# arduino_uno_with_rs232.net
KiCad netlist of a schematic drawn in EAGLE
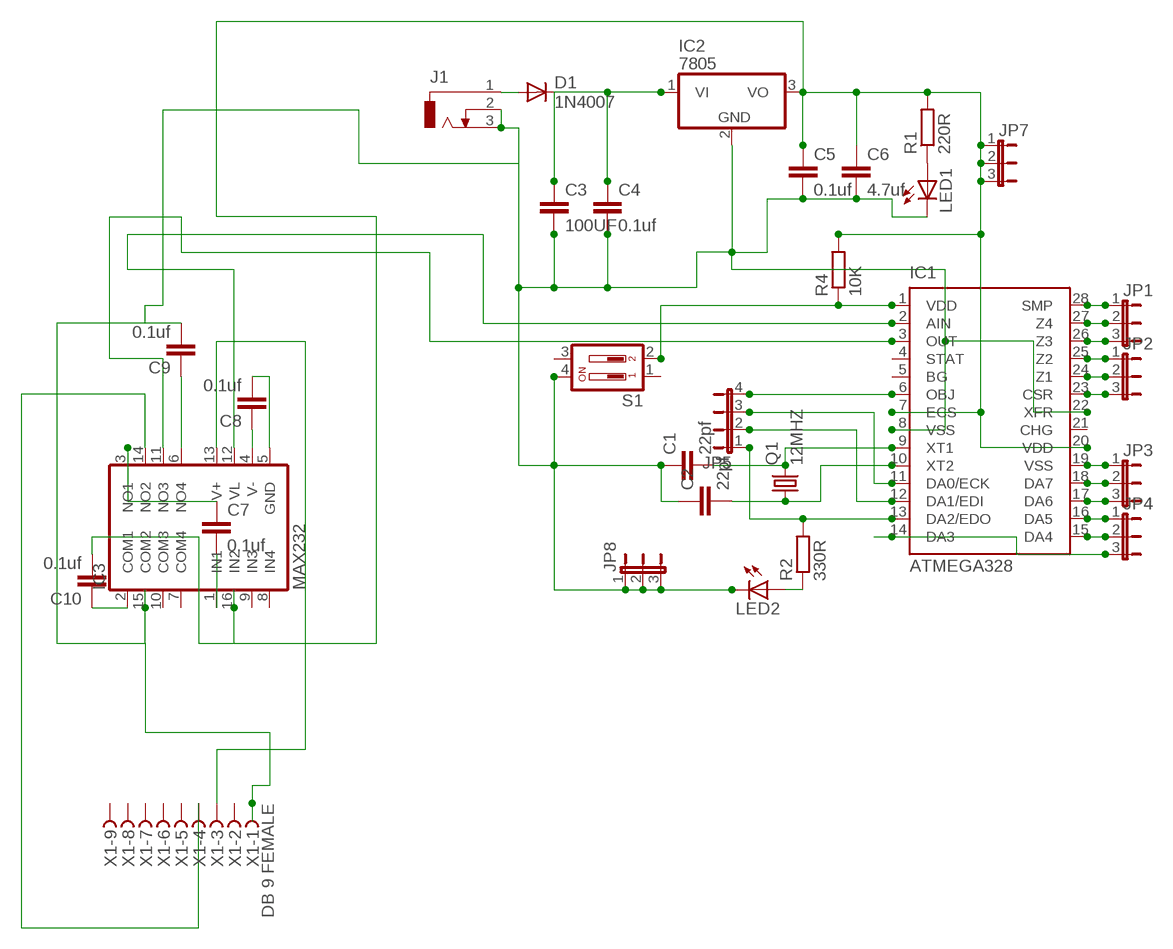
[diagram p0: schematic, sheet 1]

(export (version "E")
  (design (tool "Eeschema 10.0.6"))
  (components
    (comp (ref "C1")
      (value "22pf")
      (footprint "eagle-import:C2.5-2")
      (libsource (lib "eagle-import") (part "C2.5/2"))
    )
    (comp (ref "C2")
      (value "22pf")
      (footprint "eagle-import:C2.5-2")
      (libsource (lib "eagle-import") (part "C2.5/2"))
    )
    (comp (ref "C3")
      (value "100UF")
      (footprint "eagle-import:C2.5-2")
      (libsource (lib "eagle-import") (part "C2.5/2"))
    )
    (comp (ref "C4")
      (value "0.1uf")
      (footprint "eagle-import:C2.5-2")
      (libsource (lib "eagle-import") (part "C2.5/2"))
    )
    (comp (ref "C5")
      (value "0.1uf")
      (footprint "eagle-import:C2.5-2")
      (libsource (lib "eagle-import") (part "C2.5/2"))
    )
    (comp (ref "C6")
      (value "4.7uf")
      (footprint "eagle-import:C2.5-2")
      (libsource (lib "eagle-import") (part "C2.5/2"))
    )
    (comp (ref "C7")
      (value "0.1uf")
      (footprint "eagle-import:C2.5-3")
      (libsource (lib "eagle-import") (part "C2,5-3"))
    )
    (comp (ref "C8")
      (value "0.1uf")
      (footprint "eagle-import:C2.5-3")
      (libsource (lib "eagle-import") (part "C2,5-3"))
    )
    (comp (ref "C9")
      (value "0.1uf")
      (footprint "eagle-import:C2.5-3")
      (libsource (lib "eagle-import") (part "C2,5-3"))
    )
    (comp (ref "C10")
      (value "0.1uf")
      (footprint "eagle-import:C2.5-3")
      (libsource (lib "eagle-import") (part "C2,5-3"))
    )
    (comp (ref "D1")
      (value "1N4007")
      (footprint "eagle-import:DO41-10")
      (libsource (lib "eagle-import") (part "1N4004"))
    )
    (comp (ref "IC1")
      (value "ATMEGA328")
      (footprint "eagle-import:DIL28-3")
      (libsource (lib "eagle-import") (part "QT9701BD"))
    )
    (comp (ref "IC2")
      (value "7805")
      (footprint "eagle-import:TO220V")
      (libsource (lib "eagle-import") (part "78TV6"))
    )
    (comp (ref "IC3")
      (value "MAX232")
      (footprint "eagle-import:DIL16")
      (fields (field (name "MPN") "MAX313EPE+"))
      (libsource (lib "eagle-import") (part "MAX313PEE"))
    )
    (comp (ref "J1")
      (value "DCJ0303")
      (footprint "eagle-import:DCJ0303")
      (libsource (lib "eagle-import") (part "DCJ0303"))
    )
    (comp (ref "JP1")
      (value "JP2E")
      (footprint "eagle-import:JP2")
      (libsource (lib "eagle-import") (part "JP2E"))
    )
    (comp (ref "JP2")
      (value "JP2E")
      (footprint "eagle-import:JP2")
      (libsource (lib "eagle-import") (part "JP2E"))
    )
    (comp (ref "JP3")
      (value "JP2E")
      (footprint "eagle-import:JP2")
      (libsource (lib "eagle-import") (part "JP2E"))
    )
    (comp (ref "JP4")
      (value "JP2E")
      (footprint "eagle-import:JP2")
      (libsource (lib "eagle-import") (part "JP2E"))
    )
    (comp (ref "JP5")
      (value "JP4E")
      (footprint "eagle-import:JP4")
      (libsource (lib "eagle-import") (part "JP4E"))
    )
    (comp (ref "JP7")
      (value "JP2E")
      (footprint "eagle-import:JP2")
      (libsource (lib "eagle-import") (part "JP2E"))
    )
    (comp (ref "JP8")
      (value "JP2E")
      (footprint "eagle-import:JP2")
      (libsource (lib "eagle-import") (part "JP2E"))
    )
    (comp (ref "LED1")
      (value "LED3MM")
      (footprint "eagle-import:LED3MM")
      (libsource (lib "eagle-import") (part "LED3MM"))
    )
    (comp (ref "LED2")
      (value "LED3MM")
      (footprint "eagle-import:LED3MM")
      (libsource (lib "eagle-import") (part "LED3MM"))
    )
    (comp (ref "Q1")
      (value "12MHZ")
      (footprint "eagle-import:HC49_S")
      (libsource (lib "eagle-import") (part "CRYSTALHC49S"))
    )
    (comp (ref "R1")
      (value "220R")
      (footprint "eagle-import:0207_10")
      (libsource (lib "eagle-import") (part "R-EU_0207/10"))
    )
    (comp (ref "R2")
      (value "330R")
      (footprint "eagle-import:0207_10")
      (libsource (lib "eagle-import") (part "R-EU_0207/10"))
    )
    (comp (ref "R4")
      (value "10K")
      (footprint "eagle-import:0207_10")
      (libsource (lib "eagle-import") (part "R-EU_0207/10"))
    )
    (comp (ref "S1")
      (value "DP02")
      (footprint "eagle-import:DP-02")
      (fields (field (name "MPN") "MCDP02"))
      (libsource (lib "eagle-import") (part "DP02"))
    )
    (comp (ref "X1")
      (value "DB 9 FEMALE")
      (footprint "eagle-import:H2M09ST")
      (libsource (lib "eagle-import") (part "D-SUB9-H2M09ST"))
    )
  )
  (nets
    (net (code "1") (name "Net-(D1-PadA)") (class "Default")
      (node (ref "D1") (pin "A") (pinfunction "A_A") (pintype "passive"))
      (node (ref "J1") (pin "1") (pinfunction "1_1") (pintype "passive"))
    )
    (net (code "2") (name "Net-(IC1-AIN)") (class "Default")
      (node (ref "IC1") (pin "2") (pinfunction "AIN_2") (pintype "input"))
      (node (ref "IC3") (pin "12") (pinfunction "VL_12") (pintype "power_in"))
    )
    (net (code "3") (name "Net-(IC1-CSR)") (class "Default")
      (node (ref "IC1") (pin "23") (pinfunction "CSR_23") (pintype "output"))
      (node (ref "JP2") (pin "3") (pinfunction "3_3") (pintype "passive"))
    )
    (net (code "4") (name "Net-(IC1-DA0{slash}ECK)") (class "Default")
      (node (ref "IC1") (pin "11") (pinfunction "DA0/ECK_11") (pintype "output"))
      (node (ref "JP5") (pin "3") (pinfunction "3_3") (pintype "passive"))
    )
    (net (code "5") (name "Net-(IC1-DA1{slash}EDI)") (class "Default")
      (node (ref "IC1") (pin "12") (pinfunction "DA1/EDI_12") (pintype "output"))
      (node (ref "JP5") (pin "2") (pinfunction "2_2") (pintype "passive"))
    )
    (net (code "6") (name "Net-(IC1-DA2{slash}EDO)") (class "Default")
      (node (ref "IC1") (pin "13") (pinfunction "DA2/EDO_13") (pintype "output"))
      (node (ref "JP5") (pin "1") (pinfunction "1_1") (pintype "passive"))
      (node (ref "R2") (pin "2") (pinfunction "2_2") (pintype "passive"))
    )
    (net (code "7") (name "Net-(IC1-DA3)") (class "Default")
      (node (ref "IC1") (pin "14") (pinfunction "DA3_14") (pintype "output"))
      (node (ref "JP4") (pin "3") (pinfunction "3_3") (pintype "passive"))
    )
    (net (code "8") (name "Net-(IC1-DA4)") (class "Default")
      (node (ref "IC1") (pin "15") (pinfunction "DA4_15") (pintype "output"))
      (node (ref "JP4") (pin "2") (pinfunction "2_2") (pintype "passive"))
    )
    (net (code "9") (name "Net-(IC1-DA5)") (class "Default")
      (node (ref "IC1") (pin "16") (pinfunction "DA5_16") (pintype "output"))
      (node (ref "JP4") (pin "1") (pinfunction "1_1") (pintype "passive"))
    )
    (net (code "10") (name "Net-(IC1-DA6)") (class "Default")
      (node (ref "IC1") (pin "17") (pinfunction "DA6_17") (pintype "output"))
      (node (ref "JP3") (pin "3") (pinfunction "3_3") (pintype "passive"))
    )
    (net (code "11") (name "Net-(IC1-DA7)") (class "Default")
      (node (ref "IC1") (pin "18") (pinfunction "DA7_18") (pintype "output"))
      (node (ref "JP3") (pin "2") (pinfunction "2_2") (pintype "passive"))
    )
    (net (code "12") (name "Net-(IC1-ECS)") (class "Default")
      (node (ref "C10") (pin "2") (pinfunction "2_2") (pintype "passive"))
      (node (ref "C5") (pin "1") (pinfunction "1_1") (pintype "passive"))
      (node (ref "C6") (pin "1") (pinfunction "1_1") (pintype "passive"))
      (node (ref "IC1") (pin "20") (pinfunction "VDD_20") (pintype "input"))
      (node (ref "IC1") (pin "7") (pinfunction "ECS_7") (pintype "output"))
      (node (ref "IC2") (pin "3") (pinfunction "VO_3") (pintype "passive"))
      (node (ref "IC3") (pin "16") (pinfunction "IN2_16") (pintype "input"))
      (node (ref "JP7") (pin "1") (pinfunction "1_1") (pintype "passive"))
      (node (ref "JP7") (pin "2") (pinfunction "2_2") (pintype "passive"))
      (node (ref "JP7") (pin "3") (pinfunction "3_3") (pintype "passive"))
      (node (ref "R1") (pin "2") (pinfunction "2_2") (pintype "passive"))
      (node (ref "R4") (pin "2") (pinfunction "2_2") (pintype "passive"))
    )
    (net (code "13") (name "Net-(IC1-OBJ)") (class "Default")
      (node (ref "IC1") (pin "6") (pinfunction "OBJ_6") (pintype "input"))
      (node (ref "JP5") (pin "4") (pinfunction "4_4") (pintype "passive"))
    )
    (net (code "14") (name "Net-(IC1-OUT)") (class "Default")
      (node (ref "IC1") (pin "3") (pinfunction "OUT_3") (pintype "output"))
      (node (ref "IC3") (pin "11") (pinfunction "NO3_11") (pintype "passive"))
    )
    (net (code "15") (name "Net-(IC1-SMP)") (class "Default")
      (node (ref "IC1") (pin "28") (pinfunction "SMP_28") (pintype "output"))
      (node (ref "JP1") (pin "1") (pinfunction "1_1") (pintype "passive"))
    )
    (net (code "16") (name "Net-(IC1-VDD-Pad1)") (class "Default")
      (node (ref "IC1") (pin "1") (pinfunction "VDD_1") (pintype "input"))
      (node (ref "R4") (pin "1") (pinfunction "1_1") (pintype "passive"))
      (node (ref "S1") (pin "2") (pinfunction "2_2") (pintype "passive"))
    )
    (net (code "17") (name "Net-(IC1-VSS-Pad19)") (class "Default")
      (node (ref "IC1") (pin "19") (pinfunction "VSS_19") (pintype "input"))
      (node (ref "JP3") (pin "1") (pinfunction "1_1") (pintype "passive"))
    )
    (net (code "18") (name "Net-(IC1-XFR)") (class "Default")
      (node (ref "C1") (pin "1") (pinfunction "1_1") (pintype "passive"))
      (node (ref "C2") (pin "1") (pinfunction "1_1") (pintype "passive"))
      (node (ref "C3") (pin "2") (pinfunction "2_2") (pintype "passive"))
      (node (ref "C4") (pin "2") (pinfunction "2_2") (pintype "passive"))
      (node (ref "C5") (pin "2") (pinfunction "2_2") (pintype "passive"))
      (node (ref "C6") (pin "2") (pinfunction "2_2") (pintype "passive"))
      (node (ref "C9") (pin "2") (pinfunction "2_2") (pintype "passive"))
      (node (ref "IC1") (pin "22") (pinfunction "XFR_22") (pintype "output"))
      (node (ref "IC1") (pin "8") (pinfunction "VSS_8") (pintype "input"))
      (node (ref "IC2") (pin "2") (pinfunction "GND_2") (pintype "passive"))
      (node (ref "IC3") (pin "15") (pinfunction "COM2_15") (pintype "passive"))
      (node (ref "J1") (pin "2") (pinfunction "2_2") (pintype "passive"))
      (node (ref "J1") (pin "3") (pinfunction "3_3") (pintype "passive"))
      (node (ref "JP8") (pin "1") (pinfunction "1_1") (pintype "passive"))
      (node (ref "JP8") (pin "2") (pinfunction "2_2") (pintype "passive"))
      (node (ref "JP8") (pin "3") (pinfunction "3_3") (pintype "passive"))
      (node (ref "LED1") (pin "K") (pinfunction "C_K") (pintype "passive"))
      (node (ref "LED2") (pin "K") (pinfunction "C_K") (pintype "passive"))
      (node (ref "S1") (pin "4") (pinfunction "4_4") (pintype "passive"))
      (node (ref "X1") (pin "1") (pinfunction "F_1") (pintype "passive"))
    )
    (net (code "19") (name "Net-(IC1-XT1)") (class "Default")
      (node (ref "C1") (pin "2") (pinfunction "2_2") (pintype "passive"))
      (node (ref "IC1") (pin "9") (pinfunction "XT1_9") (pintype "input"))
      (node (ref "Q1") (pin "2") (pinfunction "2_2") (pintype "passive"))
    )
    (net (code "20") (name "Net-(IC1-XT2)") (class "Default")
      (node (ref "C2") (pin "2") (pinfunction "2_2") (pintype "passive"))
      (node (ref "IC1") (pin "10") (pinfunction "XT2_10") (pintype "output"))
      (node (ref "Q1") (pin "1") (pinfunction "1_1") (pintype "passive"))
    )
    (net (code "21") (name "Net-(IC1-Z1)") (class "Default")
      (node (ref "IC1") (pin "24") (pinfunction "Z1_24") (pintype "output"))
      (node (ref "JP2") (pin "2") (pinfunction "2_2") (pintype "passive"))
    )
    (net (code "22") (name "Net-(IC1-Z2)") (class "Default")
      (node (ref "IC1") (pin "25") (pinfunction "Z2_25") (pintype "output"))
      (node (ref "JP2") (pin "1") (pinfunction "1_1") (pintype "passive"))
    )
    (net (code "23") (name "Net-(IC1-Z3)") (class "Default")
      (node (ref "IC1") (pin "26") (pinfunction "Z3_26") (pintype "output"))
      (node (ref "JP1") (pin "3") (pinfunction "3_3") (pintype "passive"))
    )
    (net (code "24") (name "Net-(IC1-Z4)") (class "Default")
      (node (ref "IC1") (pin "27") (pinfunction "Z4_27") (pintype "output"))
      (node (ref "JP1") (pin "2") (pinfunction "2_2") (pintype "passive"))
    )
    (net (code "25") (name "Net-(IC2-VI)") (class "Default")
      (node (ref "C3") (pin "1") (pinfunction "1_1") (pintype "passive"))
      (node (ref "C4") (pin "1") (pinfunction "1_1") (pintype "passive"))
      (node (ref "D1") (pin "C") (pinfunction "C_C") (pintype "passive"))
      (node (ref "IC2") (pin "1") (pinfunction "VI_1") (pintype "input"))
    )
    (net (code "26") (name "Net-(IC3-COM1)") (class "Default")
      (node (ref "C10") (pin "1") (pinfunction "1_1") (pintype "passive"))
      (node (ref "IC3") (pin "2") (pinfunction "COM1_2") (pintype "passive"))
    )
    (net (code "27") (name "Net-(IC3-GND)") (class "Default")
      (node (ref "C8") (pin "2") (pinfunction "2_2") (pintype "passive"))
      (node (ref "IC3") (pin "5") (pinfunction "GND_5") (pintype "power_in"))
    )
    (net (code "28") (name "Net-(IC3-IN1)") (class "Default")
      (node (ref "C7") (pin "2") (pinfunction "2_2") (pintype "passive"))
      (node (ref "IC3") (pin "1") (pinfunction "IN1_1") (pintype "input"))
    )
    (net (code "29") (name "Net-(IC3-NO1)") (class "Default")
      (node (ref "C7") (pin "1") (pinfunction "1_1") (pintype "passive"))
      (node (ref "IC3") (pin "3") (pinfunction "NO1_3") (pintype "passive"))
    )
    (net (code "30") (name "Net-(IC3-NO2)") (class "Default")
      (node (ref "IC3") (pin "14") (pinfunction "NO2_14") (pintype "passive"))
      (node (ref "X1") (pin "4") (pinfunction "F_4") (pintype "passive"))
    )
    (net (code "31") (name "Net-(IC3-NO4)") (class "Default")
      (node (ref "C9") (pin "1") (pinfunction "1_1") (pintype "passive"))
      (node (ref "IC3") (pin "6") (pinfunction "NO4_6") (pintype "passive"))
    )
    (net (code "32") (name "Net-(IC3-V+)") (class "Default")
      (node (ref "IC3") (pin "13") (pinfunction "V+_13") (pintype "power_in"))
      (node (ref "X1") (pin "3") (pinfunction "F_3") (pintype "passive"))
    )
    (net (code "33") (name "Net-(IC3-V-)") (class "Default")
      (node (ref "C8") (pin "1") (pinfunction "1_1") (pintype "passive"))
      (node (ref "IC3") (pin "4") (pinfunction "V-_4") (pintype "power_in"))
    )
    (net (code "34") (name "Net-(LED1-PadA)") (class "Default")
      (node (ref "LED1") (pin "A") (pinfunction "A_A") (pintype "passive"))
      (node (ref "R1") (pin "1") (pinfunction "1_1") (pintype "passive"))
    )
    (net (code "35") (name "Net-(LED2-PadA)") (class "Default")
      (node (ref "LED2") (pin "A") (pinfunction "A_A") (pintype "passive"))
      (node (ref "R2") (pin "1") (pinfunction "1_1") (pintype "passive"))
    )
    (net (code "36") (name "unconnected-(IC1-BG-Pad5)") (class "Default")
      (node (ref "IC1") (pin "5") (pinfunction "BG_5") (pintype "input"))
    )
    (net (code "37") (name "unconnected-(IC1-CHG-Pad21)") (class "Default")
      (node (ref "IC1") (pin "21") (pinfunction "CHG_21") (pintype "output"))
    )
    (net (code "38") (name "unconnected-(IC1-STAT-Pad4)") (class "Default")
      (node (ref "IC1") (pin "4") (pinfunction "STAT_4") (pintype "output"))
    )
    (net (code "39") (name "unconnected-(IC3-COM3-Pad10)") (class "Default")
      (node (ref "IC3") (pin "10") (pinfunction "COM3_10") (pintype "passive"))
    )
    (net (code "40") (name "unconnected-(IC3-COM4-Pad7)") (class "Default")
      (node (ref "IC3") (pin "7") (pinfunction "COM4_7") (pintype "passive"))
    )
    (net (code "41") (name "unconnected-(IC3-IN3-Pad9)") (class "Default")
      (node (ref "IC3") (pin "9") (pinfunction "IN3_9") (pintype "input"))
    )
    (net (code "42") (name "unconnected-(IC3-IN4-Pad8)") (class "Default")
      (node (ref "IC3") (pin "8") (pinfunction "IN4_8") (pintype "input"))
    )
    (net (code "43") (name "unconnected-(S1-Pad1)") (class "Default")
      (node (ref "S1") (pin "1") (pinfunction "1_1") (pintype "passive"))
    )
    (net (code "44") (name "unconnected-(S1-Pad3)") (class "Default")
      (node (ref "S1") (pin "3") (pinfunction "3_3") (pintype "passive"))
    )
    (net (code "45") (name "unconnected-(X1B-F-Pad2)") (class "Default")
      (node (ref "X1") (pin "2") (pinfunction "F_2") (pintype "passive"))
    )
    (net (code "46") (name "unconnected-(X1E-F-Pad5)") (class "Default")
      (node (ref "X1") (pin "5") (pinfunction "F_5") (pintype "passive"))
    )
    (net (code "47") (name "unconnected-(X1F-F-Pad6)") (class "Default")
      (node (ref "X1") (pin "6") (pinfunction "F_6") (pintype "passive"))
    )
    (net (code "48") (name "unconnected-(X1G-F-Pad7)") (class "Default")
      (node (ref "X1") (pin "7") (pinfunction "F_7") (pintype "passive"))
    )
    (net (code "49") (name "unconnected-(X1H-F-Pad8)") (class "Default")
      (node (ref "X1") (pin "8") (pinfunction "F_8") (pintype "passive"))
    )
    (net (code "50") (name "unconnected-(X1I-F-Pad9)") (class "Default")
      (node (ref "X1") (pin "9") (pinfunction "F_9") (pintype "passive"))
    )
  )
)
